# moss-datalight-pcb.net
KiCad netlist of a schematic drawn in EasyEDA Pro
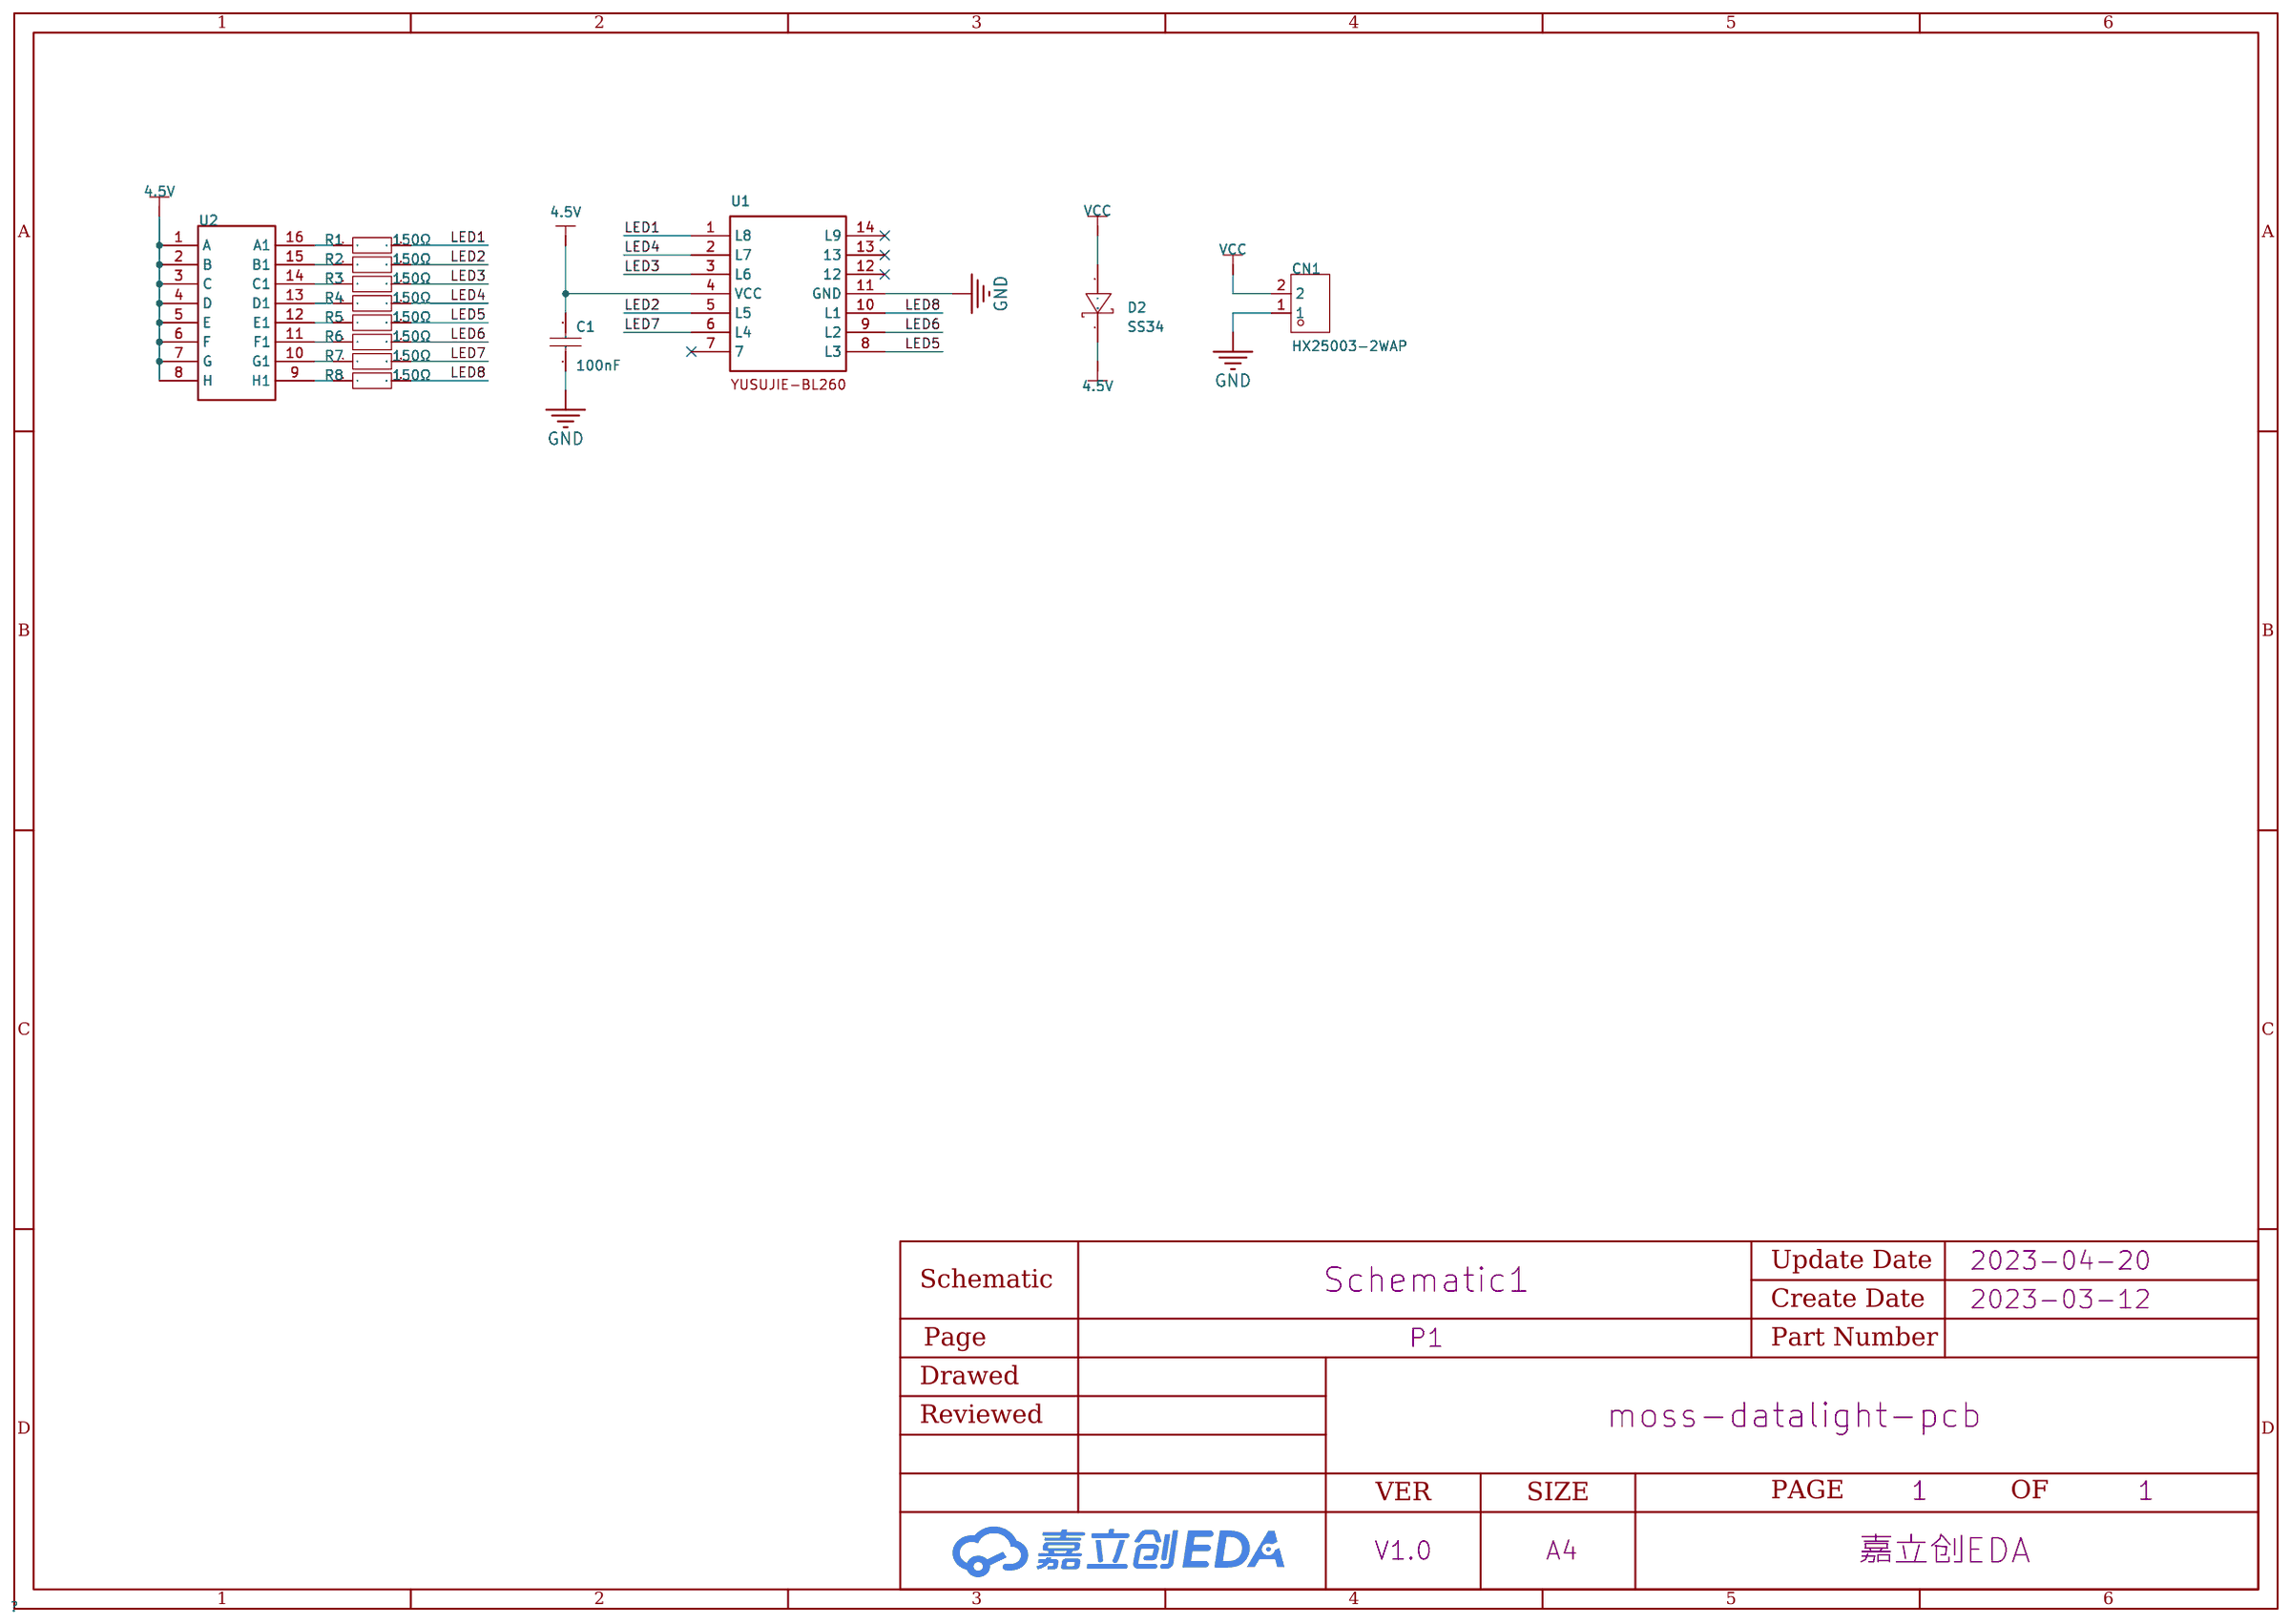
[diagram p0: schematic sheet]

(export (version "E")
  (design (tool "Eeschema 10.0.6"))
  (components
    (comp (ref "C1")
      (value "100nF")
      (footprint "easyedapro:C0402_NEW")
      (description "容值:100nF;精度:±10%;额定电压:16V;材质(温度系数):X7R;")
      (fields
        (field (name "Manufacturer Part") "CL05B104KO5NNNC")
        (field (name "Manufacturer") "SAMSUNG(三星)")
      )
      (libsource (lib "easyedapro") (part "CL05B104KO5NNNC"))
    )
    (comp (ref "CN1")
      (value "HX25003-2WAP")
      (footprint "easyedapro:CONN-TH_2P-P2.50_HX25003-2WAP")
      (description "参考系列:XH;间距:2.5mm;插针结构:1x2P;排数:1;每排PIN数:2;行距:-;公母:公型插针;安装方式:弯插;额定电流:-;工作温度范围:-;")
      (fields (field (name "Manufacturer") "HX(红星)"))
      (libsource (lib "easyedapro") (part "HX25003-2WAP"))
    )
    (comp (ref "D2")
      (value "SS34")
      (footprint "easyedapro:SMA_L4.4-W2.6-LS5.0-RD")
      (description "直流反向耐压(Vr):40V;平均整流电流(Io):3A;正向压降(Vf):500mV@3A;")
      (fields (field (name "Manufacturer") "Slkor(萨科微)"))
      (libsource (lib "easyedapro") (part "SS34_C408258"))
    )
    (comp (ref "R1")
      (value "150Ω")
      (footprint "easyedapro:R0603")
      (description "电阻类型:厚膜电阻;阻值:150Ω;精度:±1%;功率:100mW;")
      (fields
        (field (name "Manufacturer Part") "0603WAF1500T5E")
        (field (name "Manufacturer") "UNI-ROYAL(厚声)")
      )
      (libsource (lib "easyedapro") (part "0603WAF1500T5E"))
    )
    (comp (ref "R2")
      (value "150Ω")
      (footprint "easyedapro:R0603")
      (description "电阻类型:厚膜电阻;阻值:150Ω;精度:±1%;功率:100mW;")
      (fields
        (field (name "Manufacturer Part") "0603WAF1500T5E")
        (field (name "Manufacturer") "UNI-ROYAL(厚声)")
      )
      (libsource (lib "easyedapro") (part "0603WAF1500T5E"))
    )
    (comp (ref "R3")
      (value "150Ω")
      (footprint "easyedapro:R0603")
      (description "电阻类型:厚膜电阻;阻值:150Ω;精度:±1%;功率:100mW;")
      (fields
        (field (name "Manufacturer Part") "0603WAF1500T5E")
        (field (name "Manufacturer") "UNI-ROYAL(厚声)")
      )
      (libsource (lib "easyedapro") (part "0603WAF1500T5E"))
    )
    (comp (ref "R4")
      (value "150Ω")
      (footprint "easyedapro:R0603")
      (description "电阻类型:厚膜电阻;阻值:150Ω;精度:±1%;功率:100mW;")
      (fields
        (field (name "Manufacturer Part") "0603WAF1500T5E")
        (field (name "Manufacturer") "UNI-ROYAL(厚声)")
      )
      (libsource (lib "easyedapro") (part "0603WAF1500T5E"))
    )
    (comp (ref "R5")
      (value "150Ω")
      (footprint "easyedapro:R0603")
      (description "电阻类型:厚膜电阻;阻值:150Ω;精度:±1%;功率:100mW;")
      (fields
        (field (name "Manufacturer Part") "0603WAF1500T5E")
        (field (name "Manufacturer") "UNI-ROYAL(厚声)")
      )
      (libsource (lib "easyedapro") (part "0603WAF1500T5E"))
    )
    (comp (ref "R6")
      (value "150Ω")
      (footprint "easyedapro:R0603")
      (description "电阻类型:厚膜电阻;阻值:150Ω;精度:±1%;功率:100mW;")
      (fields
        (field (name "Manufacturer Part") "0603WAF1500T5E")
        (field (name "Manufacturer") "UNI-ROYAL(厚声)")
      )
      (libsource (lib "easyedapro") (part "0603WAF1500T5E"))
    )
    (comp (ref "R7")
      (value "150Ω")
      (footprint "easyedapro:R0603")
      (description "电阻类型:厚膜电阻;阻值:150Ω;精度:±1%;功率:100mW;")
      (fields
        (field (name "Manufacturer Part") "0603WAF1500T5E")
        (field (name "Manufacturer") "UNI-ROYAL(厚声)")
      )
      (libsource (lib "easyedapro") (part "0603WAF1500T5E"))
    )
    (comp (ref "R8")
      (value "150Ω")
      (footprint "easyedapro:R0603")
      (description "电阻类型:厚膜电阻;阻值:150Ω;精度:±1%;功率:100mW;")
      (fields
        (field (name "Manufacturer Part") "0603WAF1500T5E")
        (field (name "Manufacturer") "UNI-ROYAL(厚声)")
      )
      (libsource (lib "easyedapro") (part "0603WAF1500T5E"))
    )
    (comp (ref "U1")
      (value "~")
      (footprint "easyedapro:YUSUJIE-BL260")
      (description "宇思捷8路火苗模拟IC")
      (libsource (lib "easyedapro") (part "YUSUJIE-BL260"))
    )
    (comp (ref "U2")
      (value "~")
      (footprint "easyedapro:B8R")
      (description "5段红色光条数码管")
      (libsource (lib "easyedapro") (part "B8R"))
    )
  )
  (nets
    (net (code "1") (name "/LED1") (class "Default")
      (node (ref "R1") (pin "2") (pinfunction "2_2") (pintype "input"))
      (node (ref "U1") (pin "1") (pinfunction "L8_1") (pintype "input"))
    )
    (net (code "2") (name "/LED2") (class "Default")
      (node (ref "R2") (pin "2") (pinfunction "2_2") (pintype "input"))
      (node (ref "U1") (pin "5") (pinfunction "L5_5") (pintype "input"))
    )
    (net (code "3") (name "/LED3") (class "Default")
      (node (ref "R3") (pin "2") (pinfunction "2_2") (pintype "input"))
      (node (ref "U1") (pin "3") (pinfunction "L6_3") (pintype "input"))
    )
    (net (code "4") (name "/LED4") (class "Default")
      (node (ref "R4") (pin "2") (pinfunction "2_2") (pintype "input"))
      (node (ref "U1") (pin "2") (pinfunction "L7_2") (pintype "input"))
    )
    (net (code "5") (name "/LED5") (class "Default")
      (node (ref "R5") (pin "2") (pinfunction "2_2") (pintype "input"))
      (node (ref "U1") (pin "8") (pinfunction "L3_8") (pintype "input"))
    )
    (net (code "6") (name "/LED6") (class "Default")
      (node (ref "R6") (pin "2") (pinfunction "2_2") (pintype "input"))
      (node (ref "U1") (pin "9") (pinfunction "L2_9") (pintype "input"))
    )
    (net (code "7") (name "/LED7") (class "Default")
      (node (ref "R7") (pin "2") (pinfunction "2_2") (pintype "input"))
      (node (ref "U1") (pin "6") (pinfunction "L4_6") (pintype "input"))
    )
    (net (code "8") (name "/LED8") (class "Default")
      (node (ref "R8") (pin "2") (pinfunction "2_2") (pintype "input"))
      (node (ref "U1") (pin "10") (pinfunction "L1_10") (pintype "input"))
    )
    (net (code "9") (name "4.5V") (class "Default")
      (node (ref "C1") (pin "2") (pinfunction "2_2") (pintype "input"))
      (node (ref "D2") (pin "1") (pinfunction "C_1") (pintype "input"))
      (node (ref "U1") (pin "4") (pinfunction "VCC_4") (pintype "input"))
      (node (ref "U2") (pin "1") (pinfunction "A_1") (pintype "input"))
      (node (ref "U2") (pin "2") (pinfunction "B_2") (pintype "input"))
      (node (ref "U2") (pin "3") (pinfunction "C_3") (pintype "input"))
      (node (ref "U2") (pin "4") (pinfunction "D_4") (pintype "input"))
      (node (ref "U2") (pin "5") (pinfunction "E_5") (pintype "input"))
      (node (ref "U2") (pin "6") (pinfunction "F_6") (pintype "input"))
      (node (ref "U2") (pin "7") (pinfunction "G_7") (pintype "input"))
      (node (ref "U2") (pin "8") (pinfunction "H_8") (pintype "input"))
    )
    (net (code "10") (name "GND") (class "Default")
      (node (ref "C1") (pin "1") (pinfunction "1_1") (pintype "input"))
      (node (ref "CN1") (pin "1") (pinfunction "1_1") (pintype "input"))
      (node (ref "U1") (pin "11") (pinfunction "GND_11") (pintype "input"))
    )
    (net (code "11") (name "Net-(U2-A1)") (class "Default")
      (node (ref "R1") (pin "1") (pinfunction "1_1") (pintype "input"))
      (node (ref "U2") (pin "16") (pinfunction "A1_16") (pintype "input"))
    )
    (net (code "12") (name "Net-(U2-B1)") (class "Default")
      (node (ref "R2") (pin "1") (pinfunction "1_1") (pintype "input"))
      (node (ref "U2") (pin "15") (pinfunction "B1_15") (pintype "input"))
    )
    (net (code "13") (name "Net-(U2-C1)") (class "Default")
      (node (ref "R3") (pin "1") (pinfunction "1_1") (pintype "input"))
      (node (ref "U2") (pin "14") (pinfunction "C1_14") (pintype "input"))
    )
    (net (code "14") (name "Net-(U2-D1)") (class "Default")
      (node (ref "R4") (pin "1") (pinfunction "1_1") (pintype "input"))
      (node (ref "U2") (pin "13") (pinfunction "D1_13") (pintype "input"))
    )
    (net (code "15") (name "Net-(U2-E1)") (class "Default")
      (node (ref "R5") (pin "1") (pinfunction "1_1") (pintype "input"))
      (node (ref "U2") (pin "12") (pinfunction "E1_12") (pintype "input"))
    )
    (net (code "16") (name "Net-(U2-F1)") (class "Default")
      (node (ref "R6") (pin "1") (pinfunction "1_1") (pintype "input"))
      (node (ref "U2") (pin "11") (pinfunction "F1_11") (pintype "input"))
    )
    (net (code "17") (name "Net-(U2-G1)") (class "Default")
      (node (ref "R7") (pin "1") (pinfunction "1_1") (pintype "input"))
      (node (ref "U2") (pin "10") (pinfunction "G1_10") (pintype "input"))
    )
    (net (code "18") (name "Net-(U2-H1)") (class "Default")
      (node (ref "R8") (pin "1") (pinfunction "1_1") (pintype "input"))
      (node (ref "U2") (pin "9") (pinfunction "H1_9") (pintype "input"))
    )
    (net (code "19") (name "VCC") (class "Default")
      (node (ref "CN1") (pin "2") (pinfunction "2_2") (pintype "input"))
      (node (ref "D2") (pin "2") (pinfunction "A_2") (pintype "input"))
    )
    (net (code "20") (name "unconnected-(U1-L9-Pad14)") (class "Default")
      (node (ref "U1") (pin "14") (pinfunction "L9_14") (pintype "input+no_connect"))
    )
    (net (code "21") (name "unconnected-(U1-Pad7)") (class "Default")
      (node (ref "U1") (pin "7") (pinfunction "7_7") (pintype "input+no_connect"))
    )
    (net (code "22") (name "unconnected-(U1-Pad12)") (class "Default")
      (node (ref "U1") (pin "12") (pinfunction "12_12") (pintype "input+no_connect"))
    )
    (net (code "23") (name "unconnected-(U1-Pad13)") (class "Default")
      (node (ref "U1") (pin "13") (pinfunction "13_13") (pintype "input+no_connect"))
    )
  )
)
